# OWSlaveATTiny.net
KiCad netlist of a schematic drawn in EAGLE
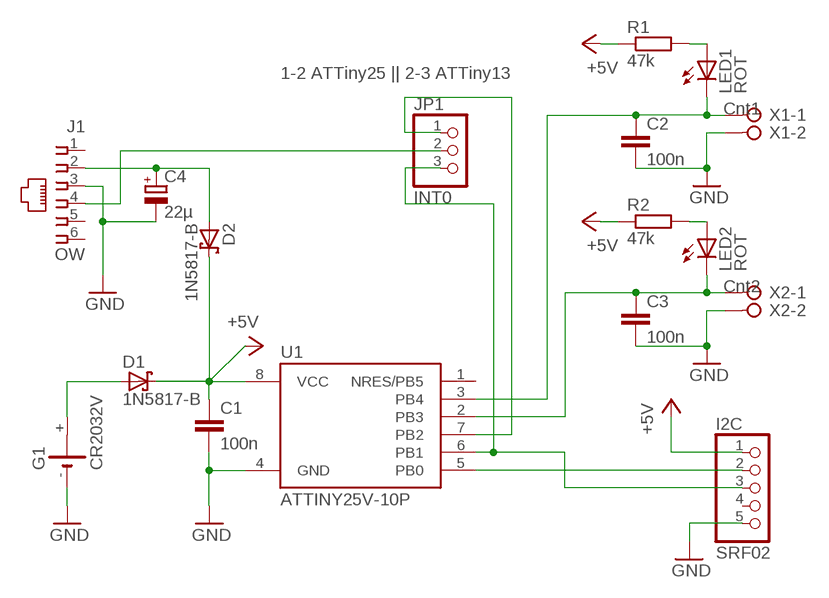
[diagram p0: schematic, sheet 1]

(export (version "E")
  (design (tool "Eeschema 10.0.6"))
  (components
    (comp (ref "C1")
      (value "100n")
      (footprint "eagle-import:C050-025X075")
      (libsource (lib "eagle-import") (part "C-EU050-025X075"))
    )
    (comp (ref "C2")
      (value "100n")
      (footprint "eagle-import:C050-025X075")
      (libsource (lib "eagle-import") (part "C-EU050-025X075"))
    )
    (comp (ref "C3")
      (value "100n")
      (footprint "eagle-import:C050-025X075")
      (libsource (lib "eagle-import") (part "C-EU050-025X075"))
    )
    (comp (ref "C4")
      (value "22µ")
      (footprint "eagle-import:E2,5-6E")
      (libsource (lib "eagle-import") (part "CPOL-EUE2,5-6E"))
    )
    (comp (ref "D1")
      (value "1N5817-B")
      (footprint "eagle-import:DO41-7.6")
      (libsource (lib "eagle-import") (part "1N5817-B"))
    )
    (comp (ref "D2")
      (value "1N5817-B")
      (footprint "eagle-import:DO41-7.6")
      (libsource (lib "eagle-import") (part "1N5817-B"))
    )
    (comp (ref "G1")
      (value "CR2032V")
      (footprint "eagle-import:CR2032V")
      (libsource (lib "eagle-import") (part "CR2032V"))
    )
    (comp (ref "I2C")
      (value "SRF02")
      (footprint "eagle-import:1X05")
      (libsource (lib "eagle-import") (part "PINHD-1X5"))
    )
    (comp (ref "J1")
      (value "OW")
      (footprint "eagle-import:520250-3")
      (fields (field (name "MF") "TYCO ELECTRONICS") (field (name "MPN") "5520250-3"))
      (libsource (lib "eagle-import") (part "520250-3"))
    )
    (comp (ref "JP1")
      (value "INT0")
      (footprint "eagle-import:1X03")
      (libsource (lib "eagle-import") (part "PINHD-1X3"))
    )
    (comp (ref "LED1")
      (value "ROT")
      (footprint "eagle-import:LED5MM")
      (libsource (lib "eagle-import") (part "LED5MM"))
    )
    (comp (ref "LED2")
      (value "ROT")
      (footprint "eagle-import:LED5MM")
      (libsource (lib "eagle-import") (part "LED5MM"))
    )
    (comp (ref "R1")
      (value "47k")
      (footprint "eagle-import:0204_7")
      (libsource (lib "eagle-import") (part "R-EU_0204/7"))
    )
    (comp (ref "R2")
      (value "47k")
      (footprint "eagle-import:0204_7")
      (libsource (lib "eagle-import") (part "R-EU_0204/7"))
    )
    (comp (ref "U1")
      (value "ATTINY25V-10P")
      (footprint "eagle-import:PDIP08_300MIL")
      (libsource (lib "eagle-import") (part "ATTINY25PV-10"))
    )
    (comp (ref "X1")
      (value "Cnt1")
      (footprint "eagle-import:W237-132")
      (libsource (lib "eagle-import") (part "W237-02P"))
    )
    (comp (ref "X2")
      (value "Cnt2")
      (footprint "eagle-import:W237-132")
      (libsource (lib "eagle-import") (part "W237-02P"))
    )
  )
  (nets
    (net (code "1") (name "+5V") (class "Default")
      (node (ref "C1") (pin "1") (pinfunction "1_1") (pintype "passive"))
      (node (ref "D1") (pin "C") (pinfunction "C_C") (pintype "passive"))
      (node (ref "D2") (pin "C") (pinfunction "C_C") (pintype "passive"))
      (node (ref "I2C") (pin "1") (pinfunction "1_1") (pintype "passive"))
      (node (ref "R1") (pin "1") (pinfunction "1_1") (pintype "passive"))
      (node (ref "R2") (pin "1") (pinfunction "1_1") (pintype "passive"))
      (node (ref "U1") (pin "8") (pinfunction "VCC_8") (pintype "power_in"))
    )
    (net (code "2") (name "GND") (class "Default")
      (node (ref "C1") (pin "2") (pinfunction "2_2") (pintype "passive"))
      (node (ref "C2") (pin "2") (pinfunction "2_2") (pintype "passive"))
      (node (ref "C3") (pin "2") (pinfunction "2_2") (pintype "passive"))
      (node (ref "C4") (pin "-") (pinfunction "-_-") (pintype "passive"))
      (node (ref "G1") (pin "-") (pinfunction "-_-") (pintype "passive"))
      (node (ref "I2C") (pin "5") (pinfunction "5_5") (pintype "passive"))
      (node (ref "J1") (pin "3") (pinfunction "3_3") (pintype "passive"))
      (node (ref "U1") (pin "4") (pinfunction "GND_4") (pintype "power_in"))
      (node (ref "X1") (pin "2") (pinfunction "KL_2") (pintype "passive"))
      (node (ref "X2") (pin "2") (pinfunction "KL_2") (pintype "passive"))
    )
    (net (code "3") (name "Net-(C4-Pad+)") (class "Default")
      (node (ref "C4") (pin "+") (pinfunction "+_+") (pintype "passive"))
      (node (ref "D2") (pin "A") (pinfunction "A_A") (pintype "passive"))
      (node (ref "J1") (pin "2") (pinfunction "2_2") (pintype "passive"))
    )
    (net (code "4") (name "Net-(D1-PadA)") (class "Default")
      (node (ref "D1") (pin "A") (pinfunction "A_A") (pintype "passive"))
      (node (ref "G1") (pin "+") (pinfunction "+_+") (pintype "passive"))
    )
    (net (code "5") (name "Net-(J1-Pad4)") (class "Default")
      (node (ref "J1") (pin "4") (pinfunction "4_4") (pintype "passive"))
      (node (ref "JP1") (pin "2") (pinfunction "2_2") (pintype "passive"))
    )
    (net (code "6") (name "Net-(LED1-C)") (class "Default")
      (node (ref "C2") (pin "1") (pinfunction "1_1") (pintype "passive"))
      (node (ref "LED1") (pin "K") (pinfunction "C_K") (pintype "passive"))
      (node (ref "U1") (pin "3") (pinfunction "PB4_3") (pintype "bidirectional"))
      (node (ref "X1") (pin "1") (pinfunction "KL_1") (pintype "passive"))
    )
    (net (code "7") (name "Net-(LED1-PadA)") (class "Default")
      (node (ref "LED1") (pin "A") (pinfunction "A_A") (pintype "passive"))
      (node (ref "R1") (pin "2") (pinfunction "2_2") (pintype "passive"))
    )
    (net (code "8") (name "Net-(LED2-C)") (class "Default")
      (node (ref "C3") (pin "1") (pinfunction "1_1") (pintype "passive"))
      (node (ref "LED2") (pin "K") (pinfunction "C_K") (pintype "passive"))
      (node (ref "U1") (pin "2") (pinfunction "PB3_2") (pintype "bidirectional"))
      (node (ref "X2") (pin "1") (pinfunction "KL_1") (pintype "passive"))
    )
    (net (code "9") (name "Net-(LED2-PadA)") (class "Default")
      (node (ref "LED2") (pin "A") (pinfunction "A_A") (pintype "passive"))
      (node (ref "R2") (pin "2") (pinfunction "2_2") (pintype "passive"))
    )
    (net (code "10") (name "Net-(U1-PB0)") (class "Default")
      (node (ref "I2C") (pin "2") (pinfunction "2_2") (pintype "passive"))
      (node (ref "U1") (pin "5") (pinfunction "PB0_5") (pintype "bidirectional"))
    )
    (net (code "11") (name "Net-(U1-PB1)") (class "Default")
      (node (ref "I2C") (pin "3") (pinfunction "3_3") (pintype "passive"))
      (node (ref "JP1") (pin "3") (pinfunction "3_3") (pintype "passive"))
      (node (ref "U1") (pin "6") (pinfunction "PB1_6") (pintype "bidirectional"))
    )
    (net (code "12") (name "Net-(U1-PB2)") (class "Default")
      (node (ref "JP1") (pin "1") (pinfunction "1_1") (pintype "passive"))
      (node (ref "U1") (pin "7") (pinfunction "PB2_7") (pintype "bidirectional"))
    )
    (net (code "13") (name "unconnected-(G1-+-Pad+@1)") (class "Default")
      (node (ref "G1") (pin "+@1") (pinfunction "+_+@1") (pintype "passive"))
    )
    (net (code "14") (name "unconnected-(I2C-Pad4)") (class "Default")
      (node (ref "I2C") (pin "4") (pinfunction "4_4") (pintype "passive"))
    )
    (net (code "15") (name "unconnected-(J1-Pad1)") (class "Default")
      (node (ref "J1") (pin "1") (pinfunction "1_1") (pintype "passive"))
    )
    (net (code "16") (name "unconnected-(J1-Pad5)") (class "Default")
      (node (ref "J1") (pin "5") (pinfunction "5_5") (pintype "passive"))
    )
    (net (code "17") (name "unconnected-(J1-Pad6)") (class "Default")
      (node (ref "J1") (pin "6") (pinfunction "6_6") (pintype "passive"))
    )
    (net (code "18") (name "unconnected-(U1-NRES{slash}PB5-Pad1)") (class "Default")
      (node (ref "U1") (pin "1") (pinfunction "NRES/PB5_1") (pintype "bidirectional"))
    )
  )
)
